# I2C_Buffer.net
KiCad netlist of a schematic drawn in Altium Designer
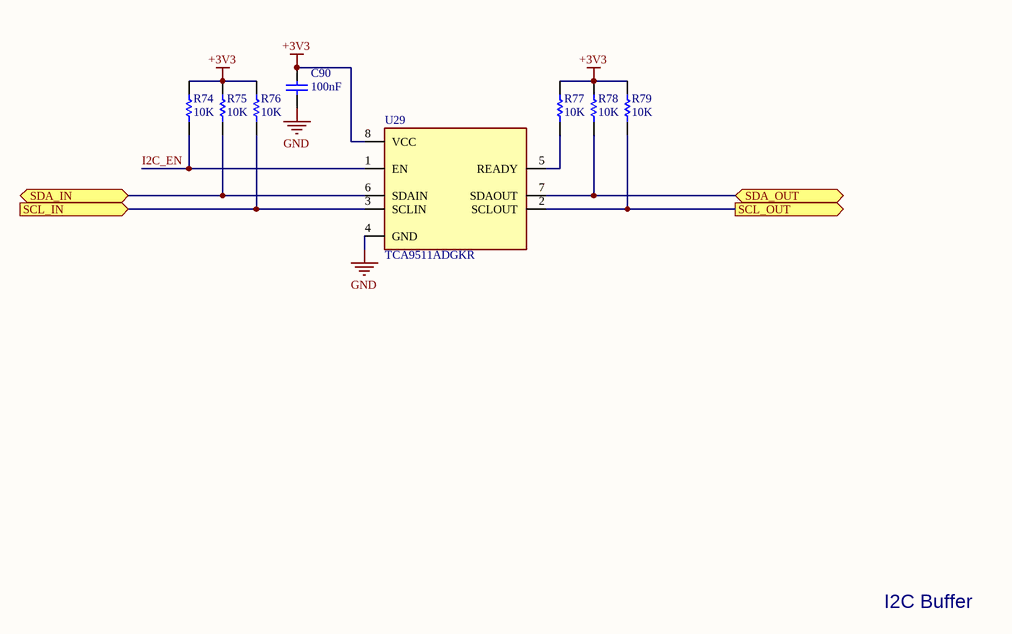
[diagram p0: I2C_Buffer.SchDoc]

(export (version "E")
  (design (tool "Eeschema 10.0.6"))
  (components
    (comp (ref "C90")
      (value "C0603C104K5RACTU")
      (footprint "CAPC0603X040")
      (description "0.1 µF ±10% 50V Ceramic Capacitor X7R 0603 (1608 Metric)")
      (fields
        (field (name "TOLERANCE") "10%")
        (field (name "DISTRIBUTOR PART NUMBER") "399-C0603C104K5RACTUCT-ND")
        (field (name "CAPACITANCE") "100nF")
      )
      (libsource (lib "Ahristi_Library") (part "C0603C104K5RACTU"))
    )
    (comp (ref "R74")
      (value "RMCF0603FT10K0")
      (footprint "RESC0603")
      (description "10 kOhms ±1% 0.1W, 1/10W Chip Resistor 0603 (1608 Metric) Automotive AEC-Q200 Thick Film")
      (fields
        (field (name "TOLERANCE") "1%")
        (field (name "DISTRIBUTOR PART NUMBER") "RMCF0603FT10K0CT-ND")
        (field (name "RESISTANCE") "10K")
      )
      (libsource (lib "Ahristi_Library") (part "RMCF0603FT10K0"))
    )
    (comp (ref "R75")
      (value "RMCF0603FT10K0")
      (footprint "RESC0603")
      (description "10 kOhms ±1% 0.1W, 1/10W Chip Resistor 0603 (1608 Metric) Automotive AEC-Q200 Thick Film")
      (fields
        (field (name "TOLERANCE") "1%")
        (field (name "DISTRIBUTOR PART NUMBER") "RMCF0603FT10K0CT-ND")
        (field (name "RESISTANCE") "10K")
      )
      (libsource (lib "Ahristi_Library") (part "RMCF0603FT10K0"))
    )
    (comp (ref "R76")
      (value "RMCF0603FT10K0")
      (footprint "RESC0603")
      (description "10 kOhms ±1% 0.1W, 1/10W Chip Resistor 0603 (1608 Metric) Automotive AEC-Q200 Thick Film")
      (fields
        (field (name "TOLERANCE") "1%")
        (field (name "DISTRIBUTOR PART NUMBER") "RMCF0603FT10K0CT-ND")
        (field (name "RESISTANCE") "10K")
      )
      (libsource (lib "Ahristi_Library") (part "RMCF0603FT10K0"))
    )
    (comp (ref "R77")
      (value "RMCF0603FT10K0")
      (footprint "RESC0603")
      (description "10 kOhms ±1% 0.1W, 1/10W Chip Resistor 0603 (1608 Metric) Automotive AEC-Q200 Thick Film")
      (fields
        (field (name "TOLERANCE") "1%")
        (field (name "DISTRIBUTOR PART NUMBER") "RMCF0603FT10K0CT-ND")
        (field (name "RESISTANCE") "10K")
      )
      (libsource (lib "Ahristi_Library") (part "RMCF0603FT10K0"))
    )
    (comp (ref "R78")
      (value "RMCF0603FT10K0")
      (footprint "RESC0603")
      (description "10 kOhms ±1% 0.1W, 1/10W Chip Resistor 0603 (1608 Metric) Automotive AEC-Q200 Thick Film")
      (fields
        (field (name "TOLERANCE") "1%")
        (field (name "DISTRIBUTOR PART NUMBER") "RMCF0603FT10K0CT-ND")
        (field (name "RESISTANCE") "10K")
      )
      (libsource (lib "Ahristi_Library") (part "RMCF0603FT10K0"))
    )
    (comp (ref "R79")
      (value "RMCF0603FT10K0")
      (footprint "RESC0603")
      (description "10 kOhms ±1% 0.1W, 1/10W Chip Resistor 0603 (1608 Metric) Automotive AEC-Q200 Thick Film")
      (fields
        (field (name "TOLERANCE") "1%")
        (field (name "DISTRIBUTOR PART NUMBER") "RMCF0603FT10K0CT-ND")
        (field (name "RESISTANCE") "10K")
      )
      (libsource (lib "Ahristi_Library") (part "RMCF0603FT10K0"))
    )
    (comp (ref "U29")
      (value "TCA9511ADGKR")
      (footprint "VSSOP-8")
      (fields (field (name "DISTRIBUTOR PART NUMBER") "296-TCA9511ADGKRCT-ND"))
      (libsource (lib "Ahristi_Library") (part "TCA9511ADGKR"))
    )
  )
  (nets
    (net (code "1") (name "+3V3") (class "Default")
      (node (ref "C90") (pin "2") (pinfunction "2_2") (pintype "passive"))
      (node (ref "R74") (pin "2") (pinfunction "2_2") (pintype "passive"))
      (node (ref "R75") (pin "2") (pinfunction "2_2") (pintype "passive"))
      (node (ref "R76") (pin "2") (pinfunction "2_2") (pintype "passive"))
      (node (ref "R77") (pin "2") (pinfunction "2_2") (pintype "passive"))
      (node (ref "R78") (pin "2") (pinfunction "2_2") (pintype "passive"))
      (node (ref "R79") (pin "2") (pinfunction "2_2") (pintype "passive"))
      (node (ref "U29") (pin "8") (pinfunction "VCC_8") (pintype "passive"))
    )
    (net (code "2") (name "/I2C_EN") (class "Default")
      (node (ref "R74") (pin "1") (pinfunction "1_1") (pintype "passive"))
      (node (ref "U29") (pin "1") (pinfunction "EN_1") (pintype "passive"))
    )
    (net (code "3") (name "/SCL_IN") (class "Default")
      (node (ref "R76") (pin "1") (pinfunction "1_1") (pintype "passive"))
      (node (ref "U29") (pin "3") (pinfunction "SCLIN_3") (pintype "passive"))
    )
    (net (code "4") (name "/SCL_OUT") (class "Default")
      (node (ref "R79") (pin "1") (pinfunction "1_1") (pintype "passive"))
      (node (ref "U29") (pin "2") (pinfunction "SCLOUT_2") (pintype "passive"))
    )
    (net (code "5") (name "/SDA_IN") (class "Default")
      (node (ref "R75") (pin "1") (pinfunction "1_1") (pintype "passive"))
      (node (ref "U29") (pin "6") (pinfunction "SDAIN_6") (pintype "passive"))
    )
    (net (code "6") (name "/SDA_OUT") (class "Default")
      (node (ref "R78") (pin "1") (pinfunction "1_1") (pintype "passive"))
      (node (ref "U29") (pin "7") (pinfunction "SDAOUT_7") (pintype "passive"))
    )
    (net (code "7") (name "GND") (class "Default")
      (node (ref "C90") (pin "1") (pinfunction "1_1") (pintype "passive"))
      (node (ref "U29") (pin "4") (pinfunction "GND_4") (pintype "passive"))
    )
    (net (code "8") (name "Net-(U29-READY)") (class "Default")
      (node (ref "R77") (pin "1") (pinfunction "1_1") (pintype "passive"))
      (node (ref "U29") (pin "5") (pinfunction "READY_5") (pintype "passive"))
    )
  )
)
